# CAN_Transciever.net
KiCad netlist of a schematic drawn in Altium Designer
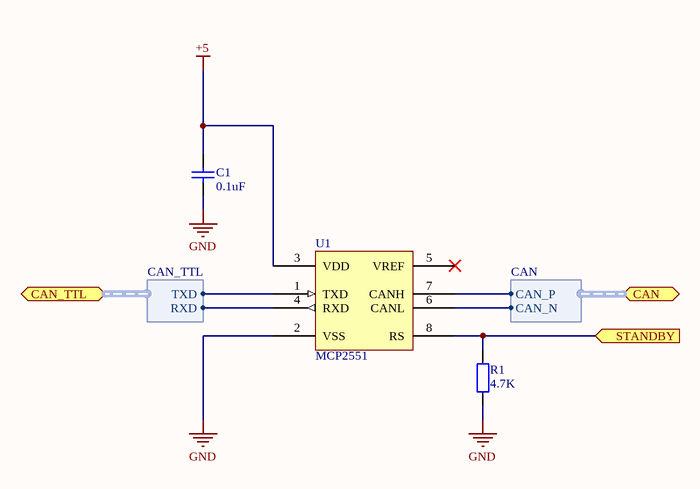
[diagram p0: CAN Transciever.SchDoc]

(export (version "E")
  (design (tool "Eeschema 10.0.6"))
  (components
    (comp (ref "C1")
      (value "0.1uF")
      (footprint "C0603")
      (description "Capacitor")
      (fields (field (name "Comment") "Cap"))
      (libsource (lib "Miscellaneous Devices") (part "Cap"))
    )
    (comp (ref "R1")
      (value "4.7K")
      (footprint "R0603")
      (description "Resistor")
      (fields (field (name "Comment") "Res"))
      (libsource (lib "Miscellaneous Devices") (part "Res2"))
    )
    (comp (ref "U1")
      (value "MCP2551")
      (footprint "MCP2551")
      (description "High-speed CAN Transceiver, 1Mb/s")
      (libsource (lib "MCP2551") (part "MCP2551"))
    )
  )
  (nets
    (net (code "3") (name "+5") (class "Default")
      (node (ref "C1") (pin "1") (pinfunction "1_1") (pintype "passive"))
      (node (ref "U1") (pin "3") (pinfunction "VDD_3") (pintype "power_in"))
    )
    (net (code "4") (name "/CAN_N") (class "Default")
      (node (ref "U1") (pin "6") (pinfunction "CANL_6") (pintype "passive"))
    )
    (net (code "5") (name "/CAN_P") (class "Default")
      (node (ref "U1") (pin "7") (pinfunction "CANH_7") (pintype "passive"))
    )
    (net (code "6") (name "/RXD") (class "Default")
      (node (ref "U1") (pin "4") (pinfunction "RXD_4") (pintype "output"))
    )
    (net (code "7") (name "/STANDBY") (class "Default")
      (node (ref "R1") (pin "2") (pinfunction "2_2") (pintype "passive"))
      (node (ref "U1") (pin "8") (pinfunction "RS_8") (pintype "passive"))
    )
    (net (code "8") (name "/TXD") (class "Default")
      (node (ref "U1") (pin "1") (pinfunction "TXD_1") (pintype "input"))
    )
    (net (code "11") (name "GND") (class "Default")
      (node (ref "C1") (pin "2") (pinfunction "2_2") (pintype "passive"))
      (node (ref "R1") (pin "1") (pinfunction "1_1") (pintype "passive"))
      (node (ref "U1") (pin "2") (pinfunction "VSS_2") (pintype "power_in"))
    )
    (net (code "12") (name "unconnected-(U1-VREF-Pad5)") (class "Default")
      (node (ref "U1") (pin "5") (pinfunction "VREF_5") (pintype "passive+no_connect"))
    )
  )
)
